# DigitalIO.net
KiCad netlist of a schematic drawn in Altium Designer
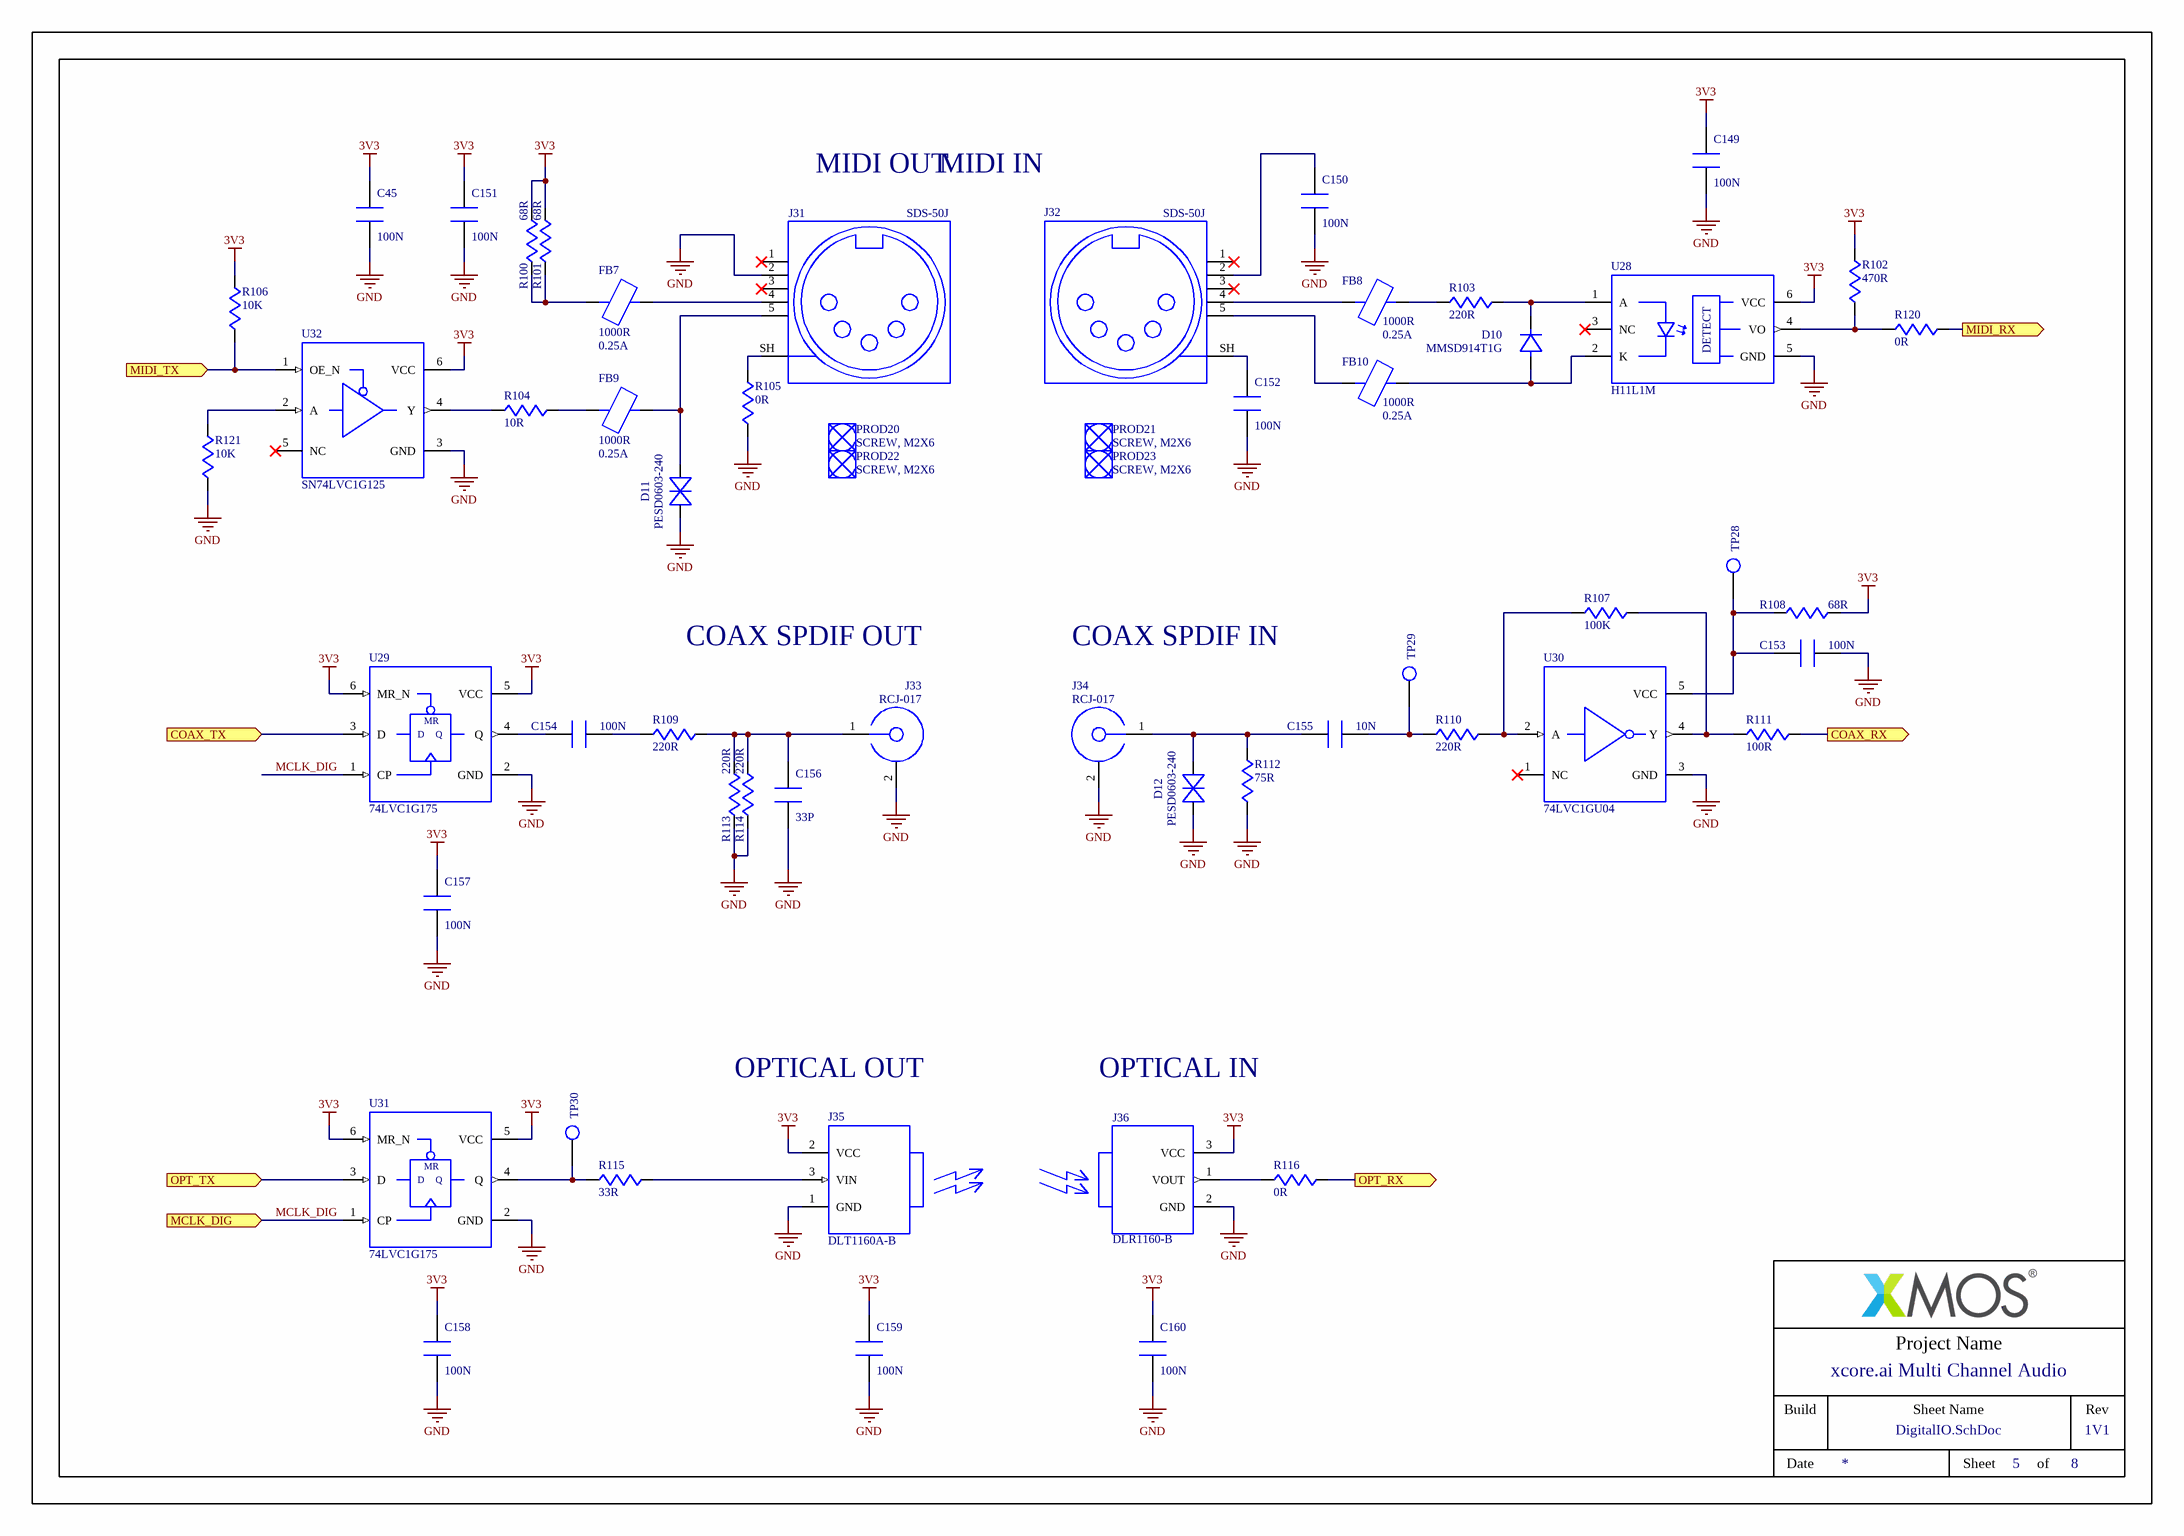
[diagram p0: DigitalIO.SchDoc]

(export (version "E")
  (design (tool "Eeschema 10.0.6"))
  (components
    (comp (ref "C45")
      (value "100N")
      (footprint "CAPC1005X55N")
      (description "CHIP CAPACITOR, CERAMIC, 100NF, 16V, 10%, X7R, 0402")
      (fields (field (name "PART NUMBER") "STD-06-0048") (field (name "TOLERANCE") "10%"))
      (libsource (lib "JG_StandardLibrary") (part "CAP_NP"))
    )
    (comp (ref "C149")
      (value "100N")
      (footprint "CAPC1005X55N")
      (description "CHIP CAPACITOR, CERAMIC, 100NF, 16V, 10%, X7R, 0402")
      (fields (field (name "PART NUMBER") "STD-06-0048") (field (name "TOLERANCE") "10%"))
      (libsource (lib "JG_StandardLibrary") (part "CAP_NP"))
    )
    (comp (ref "C150")
      (value "100N")
      (footprint "CAPC1608X90N")
      (description "CHIP CAPACITOR, CERAMIC, 100NF, 50V, 10%, X7R, 0603")
      (fields (field (name "PART NUMBER") "STD-06-0073") (field (name "TOLERANCE") "10%"))
      (libsource (lib "JG_StandardLibrary") (part "CAP_NP"))
    )
    (comp (ref "C151")
      (value "100N")
      (footprint "CAPC1005X55N")
      (description "CHIP CAPACITOR, CERAMIC, 100NF, 16V, 10%, X7R, 0402")
      (fields (field (name "PART NUMBER") "STD-06-0048") (field (name "TOLERANCE") "10%"))
      (libsource (lib "JG_StandardLibrary") (part "CAP_NP"))
    )
    (comp (ref "C152")
      (value "100N")
      (footprint "CAPC1608X90N")
      (description "CHIP CAPACITOR, CERAMIC, 100NF, 50V, 10%, X7R, 0603")
      (fields (field (name "PART NUMBER") "STD-06-0073") (field (name "TOLERANCE") "10%"))
      (libsource (lib "JG_StandardLibrary") (part "CAP_NP"))
    )
    (comp (ref "C153")
      (value "100N")
      (footprint "CAPC1005X55N")
      (description "CHIP CAPACITOR, CERAMIC, 100NF, 16V, 10%, X7R, 0402")
      (fields (field (name "PART NUMBER") "STD-06-0048") (field (name "TOLERANCE") "10%"))
      (libsource (lib "JG_StandardLibrary") (part "CAP_NP"))
    )
    (comp (ref "C154")
      (value "100N")
      (footprint "CAPC1005X55N")
      (description "CHIP CAPACITOR, CERAMIC, 100NF, 16V, 10%, X7R, 0402")
      (fields (field (name "PART NUMBER") "STD-06-0048") (field (name "TOLERANCE") "10%"))
      (libsource (lib "JG_StandardLibrary") (part "CAP_NP"))
    )
    (comp (ref "C155")
      (value "10N")
      (footprint "CAPC1005X55N")
      (description "CHIP CAPACITOR, CERAMIC, 10NF, 50V, 10%, X7R, 0402")
      (fields (field (name "PART NUMBER") "STD-06-0042") (field (name "TOLERANCE") "10%"))
      (libsource (lib "JG_StandardLibrary") (part "CAP_NP"))
    )
    (comp (ref "C156")
      (value "33P")
      (footprint "CAPC1005X55N")
      (description "CHIP CAPACITOR, CERAMIC, 33PF, 50V, 5%, NP0, 0402")
      (fields (field (name "PART NUMBER") "STD-06-0019") (field (name "TOLERANCE") "5%"))
      (libsource (lib "JG_StandardLibrary") (part "CAP_NP"))
    )
    (comp (ref "C157")
      (value "100N")
      (footprint "CAPC1005X55N")
      (description "CHIP CAPACITOR, CERAMIC, 100NF, 16V, 10%, X7R, 0402")
      (fields (field (name "PART NUMBER") "STD-06-0048") (field (name "TOLERANCE") "10%"))
      (libsource (lib "JG_StandardLibrary") (part "CAP_NP"))
    )
    (comp (ref "C158")
      (value "100N")
      (footprint "CAPC1005X55N")
      (description "CHIP CAPACITOR, CERAMIC, 100NF, 16V, 10%, X7R, 0402")
      (fields (field (name "PART NUMBER") "STD-06-0048") (field (name "TOLERANCE") "10%"))
      (libsource (lib "JG_StandardLibrary") (part "CAP_NP"))
    )
    (comp (ref "C159")
      (value "100N")
      (footprint "CAPC1005X55N")
      (description "CHIP CAPACITOR, CERAMIC, 100NF, 16V, 10%, X7R, 0402")
      (fields (field (name "PART NUMBER") "STD-06-0048") (field (name "TOLERANCE") "10%"))
      (libsource (lib "JG_StandardLibrary") (part "CAP_NP"))
    )
    (comp (ref "C160")
      (value "100N")
      (footprint "CAPC1005X55N")
      (description "CHIP CAPACITOR, CERAMIC, 100NF, 16V, 10%, X7R, 0402")
      (fields (field (name "PART NUMBER") "STD-06-0048") (field (name "TOLERANCE") "10%"))
      (libsource (lib "JG_StandardLibrary") (part "CAP_NP"))
    )
    (comp (ref "D10")
      (value "MMSD914T1G")
      (footprint "SOD3716X135N")
      (description "Diode, 100V, 0.2A, SOD123")
      (fields (field (name "PART NUMBER") "GEN-16-0055") (field (name "MANUFACTURER") "ON Semiconductor"))
      (libsource (lib "JG_GeneralLibrary") (part "DIODE"))
    )
    (comp (ref "D11")
      (value "PESD0603-240")
      (footprint "RESC1608X55N")
      (description "Polymer ESD Protection Device, 24V Stand-Off, 0.25pF, 0603")
      (fields (field (name "PART NUMBER") "GEN-16-0011") (field (name "MANUFACTURER") "Tyco"))
      (libsource (lib "JG_GeneralLibrary") (part "PESD"))
    )
    (comp (ref "D12")
      (value "PESD0603-240")
      (footprint "RESC1608X55N")
      (description "Polymer ESD Protection Device, 24V Stand-Off, 0.25pF, 0603")
      (fields (field (name "PART NUMBER") "GEN-16-0011") (field (name "MANUFACTURER") "Tyco"))
      (libsource (lib "JG_GeneralLibrary") (part "PESD"))
    )
    (comp (ref "FB7")
      (value "1000R")
      (footprint "INDC1005X55N")
      (description "Ferrite Bead, 1000R AT 100MHz, For Signal Lines, 0402, 0.25A")
      (fields
        (field (name "PART NUMBER") "GEN-04-0019")
        (field (name "RATED CURRENT") "0.25A")
        (field (name "MANUFACTURER") "Murata")
      )
      (libsource (lib "JG_GeneralLibrary") (part "FERRITE"))
    )
    (comp (ref "FB8")
      (value "1000R")
      (footprint "INDC1005X55N")
      (description "Ferrite Bead, 1000R AT 100MHz, For Signal Lines, 0402, 0.25A")
      (fields
        (field (name "PART NUMBER") "GEN-04-0019")
        (field (name "RATED CURRENT") "0.25A")
        (field (name "MANUFACTURER") "Murata")
      )
      (libsource (lib "JG_GeneralLibrary") (part "FERRITE"))
    )
    (comp (ref "FB9")
      (value "1000R")
      (footprint "INDC1005X55N")
      (description "Ferrite Bead, 1000R AT 100MHz, For Signal Lines, 0402, 0.25A")
      (fields
        (field (name "PART NUMBER") "GEN-04-0019")
        (field (name "RATED CURRENT") "0.25A")
        (field (name "MANUFACTURER") "Murata")
      )
      (libsource (lib "JG_GeneralLibrary") (part "FERRITE"))
    )
    (comp (ref "FB10")
      (value "1000R")
      (footprint "INDC1005X55N")
      (description "Ferrite Bead, 1000R AT 100MHz, For Signal Lines, 0402, 0.25A")
      (fields
        (field (name "PART NUMBER") "GEN-04-0019")
        (field (name "RATED CURRENT") "0.25A")
        (field (name "MANUFACTURER") "Murata")
      )
      (libsource (lib "JG_GeneralLibrary") (part "FERRITE"))
    )
    (comp (ref "J31")
      (value "SDS-50J")
      (footprint "DIN_5PIN_180_RA")
      (description "Standard DIN Connector, 5 Pin, 180 degrees, PCB Mount, Right Angle, Through Hole")
      (fields (field (name "PART NUMBER") "GEN-01-0123") (field (name "MANUFACTURER") "CUI"))
      (libsource (lib "JG_GeneralLibrary") (part "CON_DIN_5PIN_180"))
    )
    (comp (ref "J32")
      (value "SDS-50J")
      (footprint "DIN_5PIN_180_RA")
      (description "Standard DIN Connector, 5 Pin, 180 degrees, PCB Mount, Right Angle, Through Hole")
      (fields (field (name "PART NUMBER") "GEN-01-0123") (field (name "MANUFACTURER") "CUI"))
      (libsource (lib "") (part "CON_DIN_5PIN_180_1"))
    )
    (comp (ref "J33")
      (value "RCJ-017")
      (footprint "CON_CUI_RCJ_017")
      (description "RCA Jack, Right Angle, Orange, Through Hole")
      (fields (field (name "PART NUMBER") "GEN-01-0124") (field (name "MANUFACTURER") "CUI"))
      (libsource (lib "") (part "COAX_2_A_1"))
    )
    (comp (ref "J34")
      (value "RCJ-017")
      (footprint "CON_CUI_RCJ_017")
      (description "RCA Jack, Right Angle, Orange, Through Hole")
      (fields (field (name "PART NUMBER") "GEN-01-0124") (field (name "MANUFACTURER") "CUI"))
      (libsource (lib "JG_GeneralLibrary") (part "COAX_2_A"))
    )
    (comp (ref "J35")
      (value "DLT1160A-B")
      (footprint "CON_OPT_AIXIN_DLX1160")
      (description "Optical Digital Audio Transmitter, Black Shutter, 16Mbps max, 2.7-5.5V, Through Hole")
      (fields
        (field (name "PART NUMBER") "GEN-01-0119")
        (field (name "MANUFACTURER") "Aixin Opto-Electrical Technology")
      )
      (libsource (lib "JG_GeneralLibrary") (part "DIG_AUD_OPT_TX_B"))
    )
    (comp (ref "J36")
      (value "DLR1160-B")
      (footprint "CON_OPT_AIXIN_DLX1160")
      (description "Optical Digital Audio Receiver, Black Shutter, 16Mbps max, 2.7-5.5V, Through Hole")
      (fields
        (field (name "PART NUMBER") "GEN-01-0120")
        (field (name "MANUFACTURER") "Aixin Opto-Electrical Technology")
      )
      (libsource (lib "JG_GeneralLibrary") (part "DIG_AUD_OPT_RX_A"))
    )
    (comp (ref "PROD20")
      (value "SCREW, M2X6")
      (description "Machine screw, M2 thread, 6mm length, Steel, BZP, Pan head Pozidriv")
      (fields (field (name "PART NUMBER") "GEN-23-0012") (field (name "MANUFACTURER") "TR Fastenings"))
      (libsource (lib "JG_GeneralLibrary") (part "PROD_ITEM"))
    )
    (comp (ref "PROD21")
      (value "SCREW, M2X6")
      (description "Machine screw, M2 thread, 6mm length, Steel, BZP, Pan head Pozidriv")
      (fields (field (name "PART NUMBER") "GEN-23-0012") (field (name "MANUFACTURER") "TR Fastenings"))
      (libsource (lib "JG_GeneralLibrary") (part "PROD_ITEM"))
    )
    (comp (ref "PROD22")
      (value "SCREW, M2X6")
      (description "Machine screw, M2 thread, 6mm length, Steel, BZP, Pan head Pozidriv")
      (fields (field (name "PART NUMBER") "GEN-23-0012") (field (name "MANUFACTURER") "TR Fastenings"))
      (libsource (lib "JG_GeneralLibrary") (part "PROD_ITEM"))
    )
    (comp (ref "PROD23")
      (value "SCREW, M2X6")
      (description "Machine screw, M2 thread, 6mm length, Steel, BZP, Pan head Pozidriv")
      (fields (field (name "PART NUMBER") "GEN-23-0012") (field (name "MANUFACTURER") "TR Fastenings"))
      (libsource (lib "JG_GeneralLibrary") (part "PROD_ITEM"))
    )
    (comp (ref "R100")
      (value "68R")
      (footprint "RESC3116X65N")
      (description "CHIP RESISTOR, 68 OHM, 0.25W, 1%, 1206")
      (fields (field (name "PART NUMBER") "STD-05-0034") (field (name "TOLERANCE") "1%"))
      (libsource (lib "JG_StandardLibrary") (part "RES"))
    )
    (comp (ref "R101")
      (value "68R")
      (footprint "RESC3116X65N")
      (description "CHIP RESISTOR, 68 OHM, 0.25W, 1%, 1206")
      (fields (field (name "PART NUMBER") "STD-05-0034") (field (name "TOLERANCE") "1%"))
      (libsource (lib "JG_StandardLibrary") (part "RES"))
    )
    (comp (ref "R102")
      (value "470R")
      (footprint "RESC1608X55N")
      (description "CHIP RESISTOR, 470 OHM, 0.1W, 1%, 0603")
      (fields (field (name "PART NUMBER") "STD-02-0054") (field (name "TOLERANCE") "1%"))
      (libsource (lib "JG_StandardLibrary") (part "RES"))
    )
    (comp (ref "R103")
      (value "220R")
      (footprint "RESC3116X65N")
      (description "CHIP RESISTOR, 220 OHM, 0.25W, 1%, 1206")
      (fields (field (name "PART NUMBER") "STD-05-0046") (field (name "TOLERANCE") "1%"))
      (libsource (lib "JG_StandardLibrary") (part "RES"))
    )
    (comp (ref "R104")
      (value "10R")
      (footprint "RESC3116X65N")
      (description "CHIP RESISTOR, 10 OHM, 0.25W, 1%, 1206")
      (fields (field (name "PART NUMBER") "STD-05-0014") (field (name "TOLERANCE") "1%"))
      (libsource (lib "JG_StandardLibrary") (part "RES"))
    )
    (comp (ref "R105")
      (value "0R")
      (footprint "RESC1608X55N")
      (description "CHIP RESISTOR, ZERO OHM JUMPER, 1A, 0603")
      (fields (field (name "PART NUMBER") "STD-02-0001") (field (name "TOLERANCE") "NA"))
      (libsource (lib "JG_StandardLibrary") (part "RES"))
    )
    (comp (ref "R106")
      (value "10K")
      (footprint "RESC1608X55N")
      (description "CHIP RESISTOR, 10K OHM, 0.1W, 1%, 0603")
      (fields (field (name "PART NUMBER") "STD-02-0086") (field (name "TOLERANCE") "1%"))
      (libsource (lib "JG_StandardLibrary") (part "RES"))
    )
    (comp (ref "R107")
      (value "100K")
      (footprint "RESC1608X55N")
      (description "CHIP RESISTOR, 100K OHM, 0.1W, 1%, 0603")
      (fields (field (name "PART NUMBER") "STD-02-0110") (field (name "TOLERANCE") "1%"))
      (libsource (lib "JG_StandardLibrary") (part "RES"))
    )
    (comp (ref "R108")
      (value "68R")
      (footprint "RESC1608X55N")
      (description "CHIP RESISTOR, 68 OHM, 0.1W, 1%, 0603")
      (fields (field (name "PART NUMBER") "STD-02-0034") (field (name "TOLERANCE") "1%"))
      (libsource (lib "JG_StandardLibrary") (part "RES"))
    )
    (comp (ref "R109")
      (value "220R")
      (footprint "RESC1608X55N")
      (description "CHIP RESISTOR, 220 OHM, 0.1W, 1%, 0603")
      (fields (field (name "PART NUMBER") "STD-02-0046") (field (name "TOLERANCE") "1%"))
      (libsource (lib "JG_StandardLibrary") (part "RES"))
    )
    (comp (ref "R110")
      (value "220R")
      (footprint "RESC1608X55N")
      (description "CHIP RESISTOR, 220 OHM, 0.1W, 1%, 0603")
      (fields (field (name "PART NUMBER") "STD-02-0046") (field (name "TOLERANCE") "1%"))
      (libsource (lib "JG_StandardLibrary") (part "RES"))
    )
    (comp (ref "R111")
      (value "100R")
      (footprint "RESC1608X55N")
      (description "CHIP RESISTOR, 100 OHM, 0.1W, 1%, 0603")
      (fields (field (name "PART NUMBER") "STD-02-0038") (field (name "TOLERANCE") "1%"))
      (libsource (lib "JG_StandardLibrary") (part "RES"))
    )
    (comp (ref "R112")
      (value "75R")
      (footprint "RESC3116X65N")
      (description "CHIP RESISTOR, 75 OHM, 0.25W, 1%, 1206")
      (fields (field (name "PART NUMBER") "STD-05-0035") (field (name "TOLERANCE") "1%"))
      (libsource (lib "JG_StandardLibrary") (part "RES"))
    )
    (comp (ref "R113")
      (value "220R")
      (footprint "RESC1608X55N")
      (description "CHIP RESISTOR, 220 OHM, 0.1W, 1%, 0603")
      (fields (field (name "PART NUMBER") "STD-02-0046") (field (name "TOLERANCE") "1%"))
      (libsource (lib "JG_StandardLibrary") (part "RES"))
    )
    (comp (ref "R114")
      (value "220R")
      (footprint "RESC1608X55N")
      (description "CHIP RESISTOR, 220 OHM, 0.1W, 1%, 0603")
      (fields (field (name "PART NUMBER") "STD-02-0046") (field (name "TOLERANCE") "1%"))
      (libsource (lib "JG_StandardLibrary") (part "RES"))
    )
    (comp (ref "R115")
      (value "33R")
      (footprint "RESC1608X55N")
      (description "CHIP RESISTOR, 33 OHM, 0.1W, 1%, 0603")
      (fields (field (name "PART NUMBER") "STD-02-0026") (field (name "TOLERANCE") "1%"))
      (libsource (lib "JG_StandardLibrary") (part "RES"))
    )
    (comp (ref "R116")
      (value "0R")
      (footprint "RESC1608X55N")
      (description "CHIP RESISTOR, ZERO OHM JUMPER, 1A, 0603")
      (fields (field (name "PART NUMBER") "STD-02-0001") (field (name "TOLERANCE") "NA"))
      (libsource (lib "JG_StandardLibrary") (part "RES"))
    )
    (comp (ref "R120")
      (value "0R")
      (footprint "RESC1608X55N")
      (description "CHIP RESISTOR, ZERO OHM JUMPER, 1A, 0603")
      (fields (field (name "PART NUMBER") "STD-02-0001") (field (name "TOLERANCE") "NA"))
      (libsource (lib "JG_StandardLibrary") (part "RES"))
    )
    (comp (ref "R121")
      (value "10K")
      (footprint "RESC1608X55N")
      (description "CHIP RESISTOR, 10K OHM, 0.1W, 1%, 0603")
      (fields (field (name "PART NUMBER") "STD-02-0086") (field (name "TOLERANCE") "1%"))
      (libsource (lib "JG_StandardLibrary") (part "RES"))
    )
    (comp (ref "TP28")
      (value "TESTPOINT")
      (footprint "TESTPOINT_SMD_1MM")
      (description "Testpoint, SMD, 1mm")
      (fields (field (name "PART NUMBER") "GEN-24-0003") (field (name "MANUFACTURER") "NA"))
      (libsource (lib "JG_GeneralLibrary") (part "TESTPOINT"))
    )
    (comp (ref "TP29")
      (value "TESTPOINT")
      (footprint "TESTPOINT_SMD_1MM")
      (description "Testpoint, SMD, 1mm")
      (fields (field (name "PART NUMBER") "GEN-24-0003") (field (name "MANUFACTURER") "NA"))
      (libsource (lib "JG_GeneralLibrary") (part "TESTPOINT"))
    )
    (comp (ref "TP30")
      (value "TESTPOINT")
      (footprint "TESTPOINT_SMD_1MM")
      (description "Testpoint, SMD, 1mm")
      (fields (field (name "PART NUMBER") "GEN-24-0003") (field (name "MANUFACTURER") "NA"))
      (libsource (lib "JG_GeneralLibrary") (part "TESTPOINT"))
    )
    (comp (ref "U28")
      (value "H11L1M")
      (footprint "IC_ONSEMI_PDIP6_646BY")
      (description "Optocoupler, Schmitt Trigger Output, 3-15V, 1.6mA Turn-On, PDIP6_SMD")
      (fields (field (name "PART NUMBER") "GEN-13-0028") (field (name "MANUFACTURER") "ON Semiconductor"))
      (libsource (lib "JG_GeneralLibrary") (part "ONSEMI_H11L1M"))
    )
    (comp (ref "U29")
      (value "74LVC1G175")
      (footprint "SOT95P280X145-6N")
      (description "Single D-Type Flip Flop with Reset, Positive Edge Trigger, LVC Series, SOT23-6 (SC-74)")
      (fields (field (name "PART NUMBER") "GEN-11-0051") (field (name "MANUFACTURER") "Nexperia"))
      (libsource (lib "JG_GeneralLibrary") (part "SINGLEGATE_175_A"))
    )
    (comp (ref "U30")
      (value "74LVC1GU04")
      (footprint "SOT23-5P95_275X110L40X37N")
      (description "Single Unbuffered Inverter, LVC Series, SOT23-5")
      (fields (field (name "PART NUMBER") "GEN-11-0047") (field (name "MANUFACTURER") "Nexperia"))
      (libsource (lib "JG_GeneralLibrary") (part "SINGLEGATE_04_A"))
    )
    (comp (ref "U31")
      (value "74LVC1G175")
      (footprint "SOT95P280X145-6N")
      (description "Single D-Type Flip Flop with Reset, Positive Edge Trigger, LVC Series, SOT23-6 (SC-74)")
      (fields (field (name "PART NUMBER") "GEN-11-0051") (field (name "MANUFACTURER") "Nexperia"))
      (libsource (lib "JG_GeneralLibrary") (part "SINGLEGATE_175_A"))
    )
    (comp (ref "U32")
      (value "SN74LVC1G125")
      (footprint "TI_R_PUSON_N6")
      (description "Single Buffer with 3-State Output, LVC Series, SON6")
      (fields (field (name "PART NUMBER") "GEN-11-0049") (field (name "MANUFACTURER") "Texas Instruments"))
      (libsource (lib "JG_GeneralLibrary") (part "SINGLEGATE_125_B"))
    )
  )
  (nets
    (net (code "1") (name "/COAX_RX") (class "Default")
      (node (ref "R111") (pin "2") (pinfunction "2_2") (pintype "passive"))
    )
    (net (code "2") (name "/COAX_TX") (class "Default")
      (node (ref "U29") (pin "3") (pinfunction "D_3") (pintype "input"))
    )
    (net (code "3") (name "/MCLK_DIG") (class "Default")
      (node (ref "U29") (pin "1") (pinfunction "CP_1") (pintype "input"))
      (node (ref "U31") (pin "1") (pinfunction "CP_1") (pintype "input"))
    )
    (net (code "4") (name "/MIDI_RX") (class "Default")
      (node (ref "R120") (pin "2") (pinfunction "2_2") (pintype "passive"))
    )
    (net (code "5") (name "/MIDI_TX") (class "Default")
      (node (ref "R106") (pin "1") (pinfunction "1_1") (pintype "passive"))
      (node (ref "U32") (pin "1") (pinfunction "OE_N_1") (pintype "input"))
    )
    (net (code "6") (name "/OPT_RX") (class "Default")
      (node (ref "R116") (pin "2") (pinfunction "2_2") (pintype "passive"))
    )
    (net (code "7") (name "/OPT_TX") (class "Default")
      (node (ref "U31") (pin "3") (pinfunction "D_3") (pintype "input"))
    )
    (net (code "8") (name "3V3") (class "Default")
      (node (ref "C149") (pin "1") (pinfunction "1_1") (pintype "passive"))
      (node (ref "C151") (pin "1") (pinfunction "1_1") (pintype "passive"))
      (node (ref "C157") (pin "1") (pinfunction "1_1") (pintype "passive"))
      (node (ref "C158") (pin "1") (pinfunction "1_1") (pintype "passive"))
      (node (ref "C159") (pin "1") (pinfunction "1_1") (pintype "passive"))
      (node (ref "C160") (pin "1") (pinfunction "1_1") (pintype "passive"))
      (node (ref "C45") (pin "1") (pinfunction "1_1") (pintype "passive"))
      (node (ref "J35") (pin "2") (pinfunction "VCC_2") (pintype "power_in"))
      (node (ref "J36") (pin "3") (pinfunction "VCC_3") (pintype "power_in"))
      (node (ref "R100") (pin "2") (pinfunction "2_2") (pintype "passive"))
      (node (ref "R101") (pin "2") (pinfunction "2_2") (pintype "passive"))
      (node (ref "R102") (pin "2") (pinfunction "2_2") (pintype "passive"))
      (node (ref "R106") (pin "2") (pinfunction "2_2") (pintype "passive"))
      (node (ref "R108") (pin "1") (pinfunction "1_1") (pintype "passive"))
      (node (ref "U28") (pin "6") (pinfunction "VCC_6") (pintype "power_in"))
      (node (ref "U29") (pin "5") (pinfunction "VCC_5") (pintype "power_in"))
      (node (ref "U29") (pin "6") (pinfunction "MR_N_6") (pintype "input"))
      (node (ref "U31") (pin "5") (pinfunction "VCC_5") (pintype "power_in"))
      (node (ref "U31") (pin "6") (pinfunction "MR_N_6") (pintype "input"))
      (node (ref "U32") (pin "6") (pinfunction "VCC_6") (pintype "power_in"))
    )
    (net (code "9") (name "GND") (class "Default")
      (node (ref "C149") (pin "2") (pinfunction "2_2") (pintype "passive"))
      (node (ref "C150") (pin "2") (pinfunction "2_2") (pintype "passive"))
      (node (ref "C151") (pin "2") (pinfunction "2_2") (pintype "passive"))
      (node (ref "C152") (pin "2") (pinfunction "2_2") (pintype "passive"))
      (node (ref "C153") (pin "2") (pinfunction "2_2") (pintype "passive"))
      (node (ref "C156") (pin "2") (pinfunction "2_2") (pintype "passive"))
      (node (ref "C157") (pin "2") (pinfunction "2_2") (pintype "passive"))
      (node (ref "C158") (pin "2") (pinfunction "2_2") (pintype "passive"))
      (node (ref "C159") (pin "2") (pinfunction "2_2") (pintype "passive"))
      (node (ref "C160") (pin "2") (pinfunction "2_2") (pintype "passive"))
      (node (ref "C45") (pin "2") (pinfunction "2_2") (pintype "passive"))
      (node (ref "D11") (pin "1") (pinfunction "1_1") (pintype "passive"))
      (node (ref "D12") (pin "1") (pinfunction "1_1") (pintype "passive"))
      (node (ref "J31") (pin "2") (pinfunction "2_2") (pintype "passive"))
      (node (ref "J33") (pin "2") (pinfunction "2_2") (pintype "passive"))
      (node (ref "J34") (pin "2") (pinfunction "2_2") (pintype "passive"))
      (node (ref "J35") (pin "1") (pinfunction "GND_1") (pintype "power_in"))
      (node (ref "J36") (pin "2") (pinfunction "GND_2") (pintype "power_in"))
      (node (ref "R105") (pin "1") (pinfunction "1_1") (pintype "passive"))
      (node (ref "R112") (pin "1") (pinfunction "1_1") (pintype "passive"))
      (node (ref "R113") (pin "1") (pinfunction "1_1") (pintype "passive"))
      (node (ref "R114") (pin "1") (pinfunction "1_1") (pintype "passive"))
      (node (ref "R121") (pin "1") (pinfunction "1_1") (pintype "passive"))
      (node (ref "U28") (pin "5") (pinfunction "GND_5") (pintype "power_in"))
      (node (ref "U29") (pin "2") (pinfunction "GND_2") (pintype "power_in"))
      (node (ref "U30") (pin "3") (pinfunction "GND_3") (pintype "power_in"))
      (node (ref "U31") (pin "2") (pinfunction "GND_2") (pintype "power_in"))
      (node (ref "U32") (pin "3") (pinfunction "GND_3") (pintype "power_in"))
    )
    (net (code "10") (name "Net-(C150-Pad1)") (class "Default")
      (node (ref "C150") (pin "1") (pinfunction "1_1") (pintype "passive"))
      (node (ref "J32") (pin "2") (pinfunction "2_2") (pintype "passive"))
    )
    (net (code "11") (name "Net-(C154-Pad2)") (class "Default")
      (node (ref "C154") (pin "2") (pinfunction "2_2") (pintype "passive"))
      (node (ref "R109") (pin "1") (pinfunction "1_1") (pintype "passive"))
    )
    (net (code "12") (name "Net-(C155-Pad1)") (class "Default")
      (node (ref "C155") (pin "1") (pinfunction "1_1") (pintype "passive"))
      (node (ref "D12") (pin "2") (pinfunction "2_2") (pintype "passive"))
      (node (ref "J34") (pin "1") (pinfunction "1_1") (pintype "passive"))
      (node (ref "R112") (pin "2") (pinfunction "2_2") (pintype "passive"))
    )
    (net (code "13") (name "Net-(C155-Pad2)") (class "Default")
      (node (ref "C155") (pin "2") (pinfunction "2_2") (pintype "passive"))
      (node (ref "R110") (pin "1") (pinfunction "1_1") (pintype "passive"))
      (node (ref "TP29") (pin "1") (pinfunction "1_1") (pintype "passive"))
    )
    (net (code "14") (name "Net-(C156-Pad1)") (class "Default")
      (node (ref "C156") (pin "1") (pinfunction "1_1") (pintype "passive"))
      (node (ref "J33") (pin "1") (pinfunction "1_1") (pintype "passive"))
      (node (ref "R109") (pin "2") (pinfunction "2_2") (pintype "passive"))
      (node (ref "R113") (pin "2") (pinfunction "2_2") (pintype "passive"))
      (node (ref "R114") (pin "2") (pinfunction "2_2") (pintype "passive"))
    )
    (net (code "15") (name "Net-(D10-A)") (class "Default")
      (node (ref "D10") (pin "2") (pinfunction "A_2") (pintype "passive"))
      (node (ref "FB10") (pin "2") (pinfunction "2_2") (pintype "passive"))
      (node (ref "U28") (pin "2") (pinfunction "K_2") (pintype "passive"))
    )
    (net (code "16") (name "Net-(D10-K)") (class "Default")
      (node (ref "D10") (pin "1") (pinfunction "K_1") (pintype "passive"))
      (node (ref "R103") (pin "2") (pinfunction "2_2") (pintype "passive"))
      (node (ref "U28") (pin "1") (pinfunction "A_1") (pintype "passive"))
    )
    (net (code "17") (name "Net-(D11-Pad2)") (class "Default")
      (node (ref "D11") (pin "2") (pinfunction "2_2") (pintype "passive"))
      (node (ref "FB9") (pin "1") (pinfunction "1_1") (pintype "passive"))
      (node (ref "J31") (pin "5") (pinfunction "5_5") (pintype "passive"))
    )
    (net (code "18") (name "Net-(FB7-Pad1)") (class "Default")
      (node (ref "FB7") (pin "1") (pinfunction "1_1") (pintype "passive"))
      (node (ref "J31") (pin "4") (pinfunction "4_4") (pintype "passive"))
    )
    (net (code "19") (name "Net-(FB7-Pad2)") (class "Default")
      (node (ref "FB7") (pin "2") (pinfunction "2_2") (pintype "passive"))
      (node (ref "R100") (pin "1") (pinfunction "1_1") (pintype "passive"))
      (node (ref "R101") (pin "1") (pinfunction "1_1") (pintype "passive"))
    )
    (net (code "20") (name "Net-(FB8-Pad1)") (class "Default")
      (node (ref "FB8") (pin "1") (pinfunction "1_1") (pintype "passive"))
      (node (ref "J32") (pin "4") (pinfunction "4_4") (pintype "passive"))
    )
    (net (code "21") (name "Net-(FB8-Pad2)") (class "Default")
      (node (ref "FB8") (pin "2") (pinfunction "2_2") (pintype "passive"))
      (node (ref "R103") (pin "1") (pinfunction "1_1") (pintype "passive"))
    )
    (net (code "22") (name "Net-(FB9-Pad2)") (class "Default")
      (node (ref "FB9") (pin "2") (pinfunction "2_2") (pintype "passive"))
      (node (ref "R104") (pin "2") (pinfunction "2_2") (pintype "passive"))
    )
    (net (code "23") (name "Net-(FB10-Pad1)") (class "Default")
      (node (ref "FB10") (pin "1") (pinfunction "1_1") (pintype "passive"))
      (node (ref "J32") (pin "5") (pinfunction "5_5") (pintype "passive"))
    )
    (net (code "24") (name "Net-(J31-SHIELD)") (class "Default")
      (node (ref "J31") (pin "SH") (pinfunction "SHIELD_SH") (pintype "passive"))
      (node (ref "R105") (pin "2") (pinfunction "2_2") (pintype "passive"))
    )
    (net (code "25") (name "Net-(J32-SHIELD)") (class "Default")
      (node (ref "C152") (pin "1") (pinfunction "1_1") (pintype "passive"))
      (node (ref "J32") (pin "SH") (pinfunction "SHIELD_SH") (pintype "passive"))
    )
    (net (code "26") (name "Net-(J35-VIN)") (class "Default")
      (node (ref "J35") (pin "3") (pinfunction "VIN_3") (pintype "input"))
      (node (ref "R115") (pin "2") (pinfunction "2_2") (pintype "passive"))
    )
    (net (code "27") (name "Net-(J36-VOUT)") (class "Default")
      (node (ref "J36") (pin "1") (pinfunction "VOUT_1") (pintype "output"))
      (node (ref "R116") (pin "1") (pinfunction "1_1") (pintype "passive"))
    )
    (net (code "28") (name "Net-(U28-VO)") (class "Default")
      (node (ref "R102") (pin "1") (pinfunction "1_1") (pintype "passive"))
      (node (ref "R120") (pin "1") (pinfunction "1_1") (pintype "passive"))
      (node (ref "U28") (pin "4") (pinfunction "VO_4") (pintype "output"))
    )
    (net (code "29") (name "Net-(U29-Q)") (class "Default")
      (node (ref "C154") (pin "1") (pinfunction "1_1") (pintype "passive"))
      (node (ref "U29") (pin "4") (pinfunction "Q_4") (pintype "output"))
    )
    (net (code "30") (name "Net-(U30-A)") (class "Default")
      (node (ref "R107") (pin "1") (pinfunction "1_1") (pintype "passive"))
      (node (ref "R110") (pin "2") (pinfunction "2_2") (pintype "passive"))
      (node (ref "U30") (pin "2") (pinfunction "A_2") (pintype "input"))
    )
    (net (code "31") (name "Net-(U30-VCC)") (class "Default")
      (node (ref "C153") (pin "1") (pinfunction "1_1") (pintype "passive"))
      (node (ref "R108") (pin "2") (pinfunction "2_2") (pintype "passive"))
      (node (ref "TP28") (pin "1") (pinfunction "1_1") (pintype "passive"))
      (node (ref "U30") (pin "5") (pinfunction "VCC_5") (pintype "power_in"))
    )
    (net (code "32") (name "Net-(U30-Y)") (class "Default")
      (node (ref "R107") (pin "2") (pinfunction "2_2") (pintype "passive"))
      (node (ref "R111") (pin "1") (pinfunction "1_1") (pintype "passive"))
      (node (ref "U30") (pin "4") (pinfunction "Y_4") (pintype "output"))
    )
    (net (code "33") (name "Net-(U31-Q)") (class "Default")
      (node (ref "R115") (pin "1") (pinfunction "1_1") (pintype "passive"))
      (node (ref "TP30") (pin "1") (pinfunction "1_1") (pintype "passive"))
      (node (ref "U31") (pin "4") (pinfunction "Q_4") (pintype "output"))
    )
    (net (code "34") (name "Net-(U32-A)") (class "Default")
      (node (ref "R121") (pin "2") (pinfunction "2_2") (pintype "passive"))
      (node (ref "U32") (pin "2") (pinfunction "A_2") (pintype "input"))
    )
    (net (code "35") (name "Net-(U32-Y)") (class "Default")
      (node (ref "R104") (pin "1") (pinfunction "1_1") (pintype "passive"))
      (node (ref "U32") (pin "4") (pinfunction "Y_4") (pintype "output"))
    )
    (net (code "36") (name "unconnected-(J31-Pad1)") (class "Default")
      (node (ref "J31") (pin "1") (pinfunction "1_1") (pintype "passive+no_connect"))
    )
    (net (code "37") (name "unconnected-(J31-Pad3)") (class "Default")
      (node (ref "J31") (pin "3") (pinfunction "3_3") (pintype "passive+no_connect"))
    )
    (net (code "38") (name "unconnected-(J32-Pad1)") (class "Default")
      (node (ref "J32") (pin "1") (pinfunction "1_1") (pintype "passive+no_connect"))
    )
    (net (code "39") (name "unconnected-(J32-Pad3)") (class "Default")
      (node (ref "J32") (pin "3") (pinfunction "3_3") (pintype "passive+no_connect"))
    )
    (net (code "40") (name "unconnected-(U28-NC-Pad3)") (class "Default")
      (node (ref "U28") (pin "3") (pinfunction "NC_3") (pintype "passive+no_connect"))
    )
    (net (code "41") (name "unconnected-(U30-NC-Pad1)") (class "Default")
      (node (ref "U30") (pin "1") (pinfunction "NC_1") (pintype "passive+no_connect"))
    )
    (net (code "42") (name "unconnected-(U32-NC-Pad5)") (class "Default")
      (node (ref "U32") (pin "5") (pinfunction "NC_5") (pintype "passive+no_connect"))
    )
  )
)
